# 23005_5.net
KiCad netlist of a schematic drawn in Altium Designer
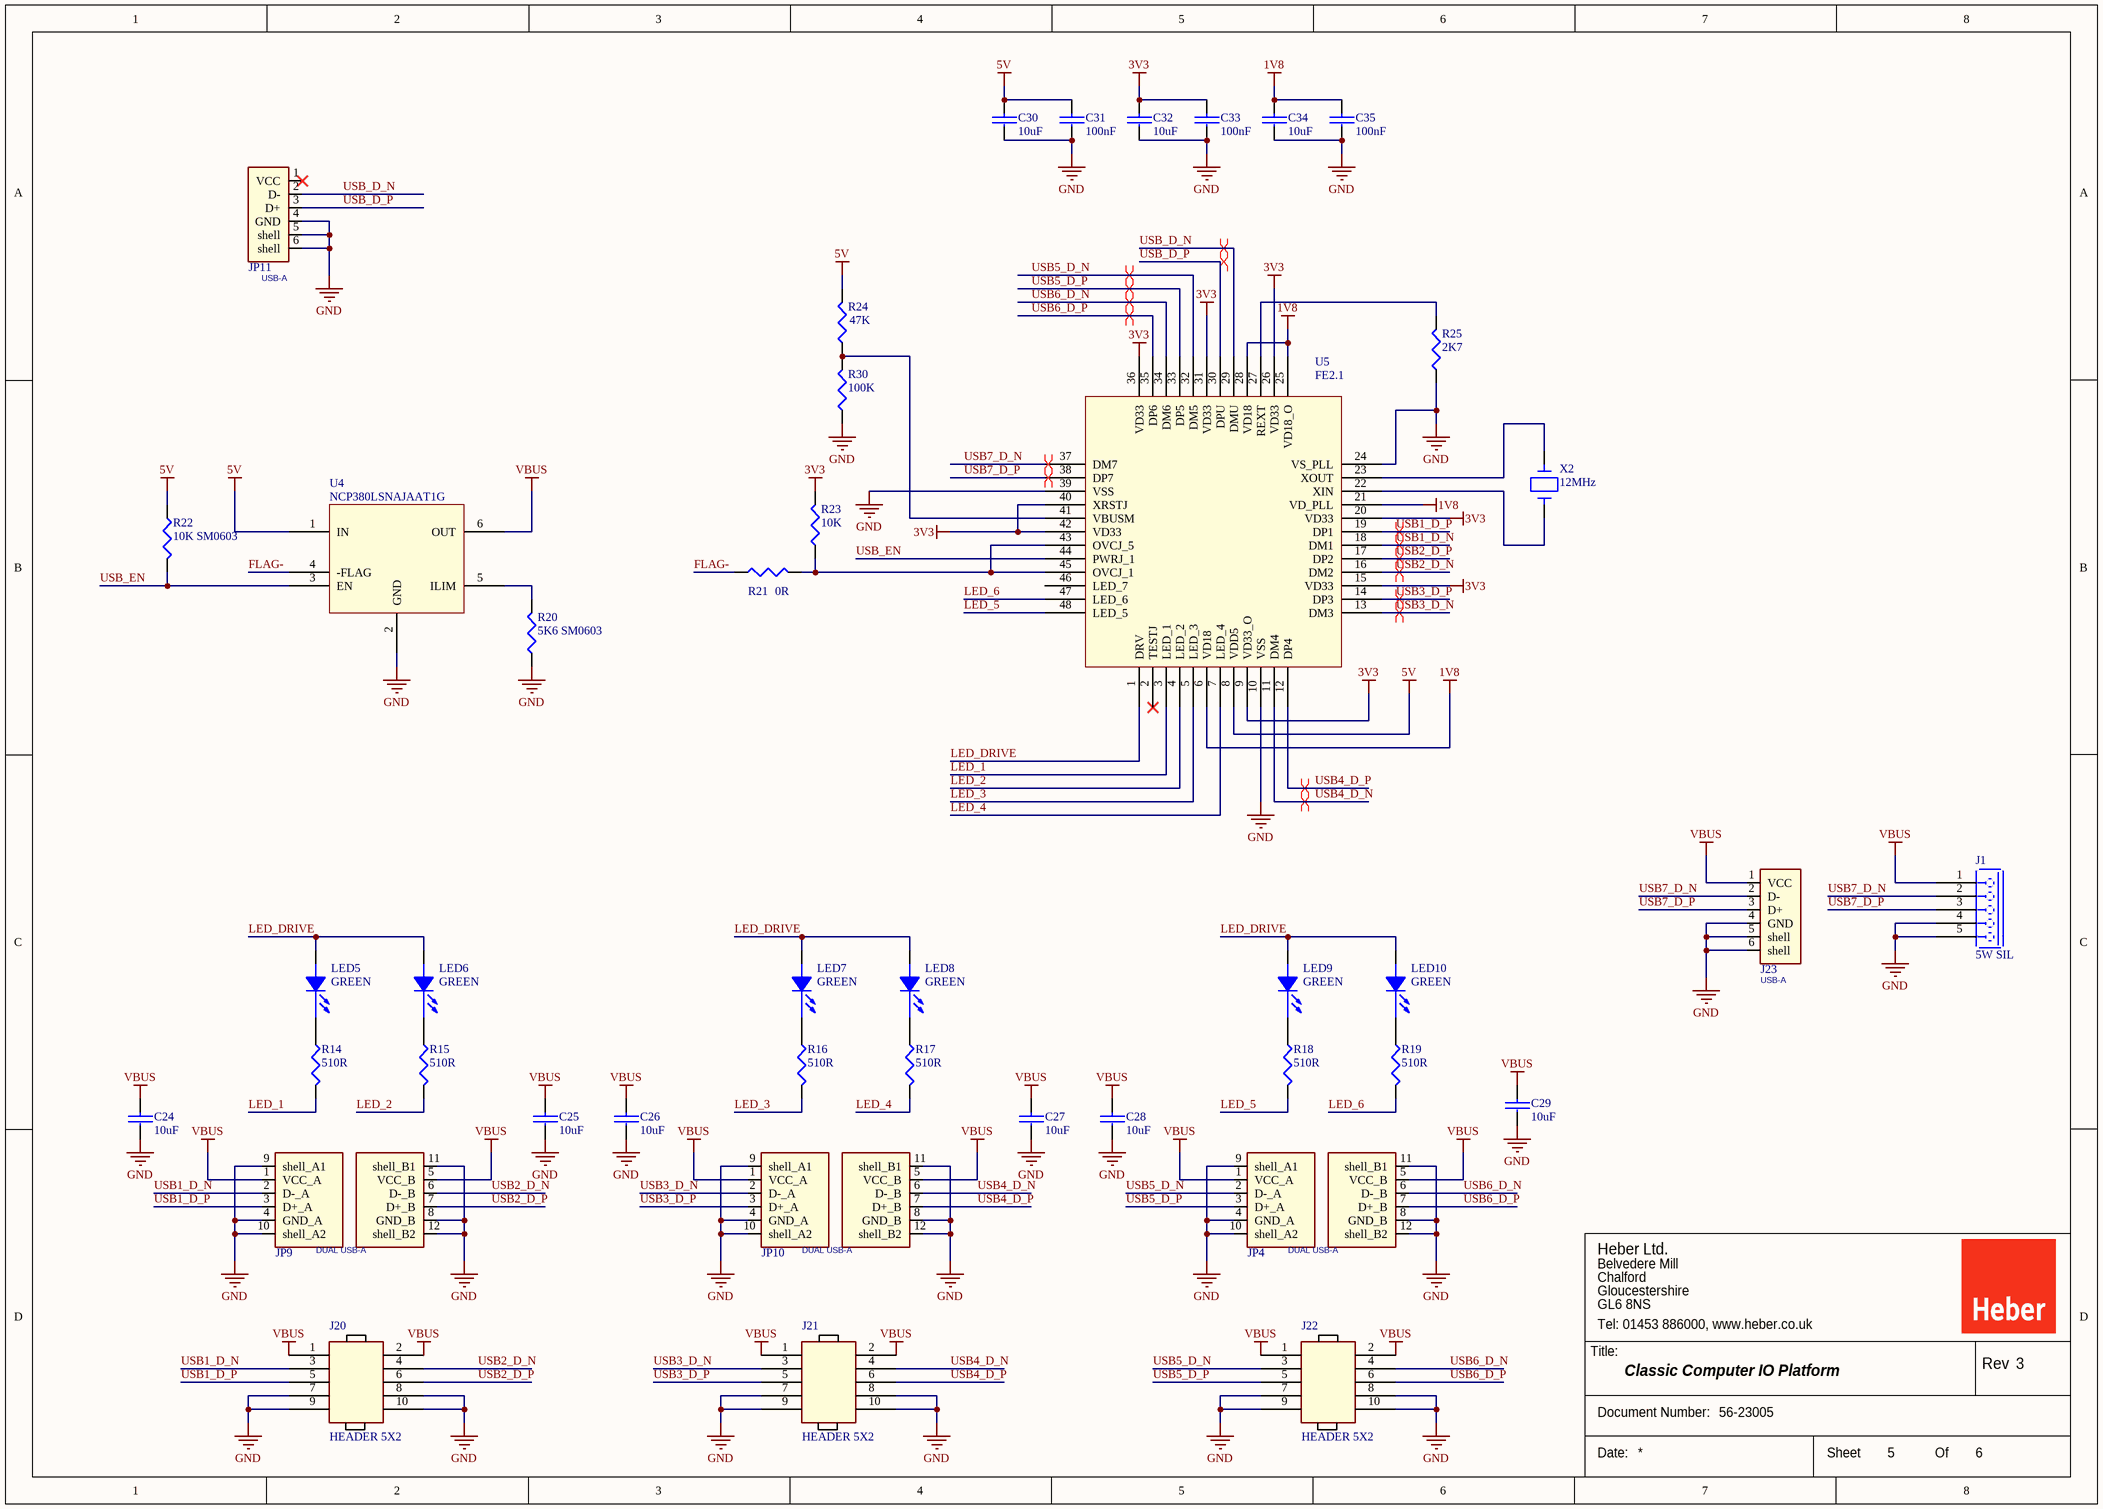
[diagram p0: 23005_5.SchDoc]

(export (version "E")
  (design (tool "Eeschema 10.0.6"))
  (components
    (comp (ref "C24") (value "10uF") (footprint "SM0805") (libsource (lib "LIBRARY1_Library") (part "C")))
    (comp (ref "C25") (value "10uF") (footprint "SM0805") (libsource (lib "LIBRARY1_Library") (part "C")))
    (comp (ref "C26") (value "10uF") (footprint "SM0805") (libsource (lib "LIBRARY1_Library") (part "C")))
    (comp (ref "C27") (value "10uF") (footprint "SM0805") (libsource (lib "LIBRARY1_Library") (part "C")))
    (comp (ref "C28") (value "10uF") (footprint "SM0805") (libsource (lib "LIBRARY1_Library") (part "C")))
    (comp (ref "C29") (value "10uF") (footprint "SM0805") (libsource (lib "LIBRARY1_Library") (part "C")))
    (comp (ref "C30") (value "10uF") (footprint "SM0805") (libsource (lib "LIBRARY1_Library") (part "C")))
    (comp (ref "C31") (value "100nF") (footprint "SM0603") (libsource (lib "LIBRARY1_Library") (part "C")))
    (comp (ref "C32") (value "10uF") (footprint "SM0805") (libsource (lib "LIBRARY1_Library") (part "C")))
    (comp (ref "C33") (value "100nF") (footprint "SM0603") (libsource (lib "LIBRARY1_Library") (part "C")))
    (comp (ref "C34") (value "10uF") (footprint "SM0805") (libsource (lib "LIBRARY1_Library") (part "C")))
    (comp (ref "C35") (value "100nF") (footprint "SM0603") (libsource (lib "LIBRARY1_Library") (part "C")))
    (comp (ref "J1")
      (value "5W SIL")
      (footprint "5WSIL")
      (libsource (lib "LIBRARY1_Library") (part "HEADER 5W SIL"))
    )
    (comp (ref "J20")
      (value "HEADER 5X2")
      (footprint "10WHDR_5X2")
      (libsource (lib "LIBRARY1_Library") (part "HEADER 5X2"))
    )
    (comp (ref "J21")
      (value "HEADER 5X2")
      (footprint "10WHDR_5X2")
      (libsource (lib "LIBRARY1_Library") (part "HEADER 5X2"))
    )
    (comp (ref "J22")
      (value "HEADER 5X2")
      (footprint "10WHDR_5X2")
      (libsource (lib "LIBRARY1_Library") (part "HEADER 5X2"))
    )
    (comp (ref "J23")
      (value "USB-A")
      (footprint "USB_WURTH_61400416021")
      (libsource (lib "LIBRARY1_Library") (part "USB-A"))
    )
    (comp (ref "JP4")
      (value "DUAL USB-A")
      (footprint "USB_STACK")
      (libsource (lib "LIBRARY1_Library") (part "USB-A_DUAL"))
    )
    (comp (ref "JP9")
      (value "DUAL USB-A")
      (footprint "USB_STACK")
      (libsource (lib "LIBRARY1_Library") (part "USB-A_DUAL"))
    )
    (comp (ref "JP10")
      (value "DUAL USB-A")
      (footprint "USB_STACK")
      (libsource (lib "LIBRARY1_Library") (part "USB-A_DUAL"))
    )
    (comp (ref "JP11")
      (value "USB-A")
      (footprint "USB_WURTH_61400416021")
      (libsource (lib "") (part "USB-A_1"))
    )
    (comp (ref "LED5")
      (value "GREEN")
      (footprint "SM0603LED_1")
      (libsource (lib "LIBRARY1_Library") (part "LED"))
    )
    (comp (ref "LED6")
      (value "GREEN")
      (footprint "SM0603LED_1")
      (libsource (lib "LIBRARY1_Library") (part "LED"))
    )
    (comp (ref "LED7")
      (value "GREEN")
      (footprint "SM0603LED_1")
      (libsource (lib "LIBRARY1_Library") (part "LED"))
    )
    (comp (ref "LED8")
      (value "GREEN")
      (footprint "SM0603LED_1")
      (libsource (lib "LIBRARY1_Library") (part "LED"))
    )
    (comp (ref "LED9")
      (value "GREEN")
      (footprint "SM0603LED_1")
      (libsource (lib "LIBRARY1_Library") (part "LED"))
    )
    (comp (ref "LED10")
      (value "GREEN")
      (footprint "SM0603LED_1")
      (libsource (lib "LIBRARY1_Library") (part "LED"))
    )
    (comp (ref "R14") (value "510R") (footprint "SM0603") (libsource (lib "LIBRARY1_Library") (part "RES")))
    (comp (ref "R15") (value "510R") (footprint "SM0603") (libsource (lib "LIBRARY1_Library") (part "RES")))
    (comp (ref "R16") (value "510R") (footprint "SM0603") (libsource (lib "LIBRARY1_Library") (part "RES")))
    (comp (ref "R17") (value "510R") (footprint "SM0603") (libsource (lib "LIBRARY1_Library") (part "RES")))
    (comp (ref "R18") (value "510R") (footprint "SM0603") (libsource (lib "LIBRARY1_Library") (part "RES")))
    (comp (ref "R19") (value "510R") (footprint "SM0603") (libsource (lib "LIBRARY1_Library") (part "RES")))
    (comp (ref "R20")
      (value "5K6 SM0603")
      (footprint "SM0603")
      (libsource (lib "LIBRARY1_Library") (part "RES"))
    )
    (comp (ref "R21") (value "0R") (footprint "SM0603") (libsource (lib "LIBRARY1_Library") (part "RES")))
    (comp (ref "R22")
      (value "10K SM0603")
      (footprint "SM0603")
      (libsource (lib "LIBRARY1_Library") (part "RES"))
    )
    (comp (ref "R23") (value "10K") (footprint "SM0603") (libsource (lib "LIBRARY1_Library") (part "RES")))
    (comp (ref "R24") (value "47K") (footprint "SM0603") (libsource (lib "LIBRARY1_Library") (part "RES")))
    (comp (ref "R25") (value "2K7") (footprint "SM0603") (libsource (lib "LIBRARY1_Library") (part "RES")))
    (comp (ref "R30") (value "100K") (footprint "SM0603") (libsource (lib "LIBRARY1_Library") (part "RES")))
    (comp (ref "U4")
      (value "NCP380LSNAJAAT1G")
      (footprint "SOT23-6LEAD")
      (libsource (lib "LIBRARY1_Library") (part "NCP380LSNAJAAT1G"))
    )
    (comp (ref "U5") (value "FE2.1") (footprint "LQFP48") (libsource (lib "LIBRARY1_Library") (part "FE2.1")))
    (comp (ref "X2") (value "12MHz") (footprint "HC49_I3") (libsource (lib "LIBRARY1_Library") (part "XTAL")))
  )
  (nets
    (net (code "1") (name "/FLAG-") (class "Default")
      (node (ref "R21") (pin "1") (pinfunction "1_1") (pintype "passive"))
      (node (ref "U4") (pin "4") (pinfunction "-FLAG_4") (pintype "passive"))
    )
    (net (code "2") (name "/LED_1") (class "Default")
      (node (ref "R14") (pin "2") (pinfunction "2_2") (pintype "passive"))
      (node (ref "U5") (pin "3") (pinfunction "LED_1_3") (pintype "passive"))
    )
    (net (code "3") (name "/LED_2") (class "Default")
      (node (ref "R15") (pin "2") (pinfunction "2_2") (pintype "passive"))
      (node (ref "U5") (pin "4") (pinfunction "LED_2_4") (pintype "passive"))
    )
    (net (code "4") (name "/LED_3") (class "Default")
      (node (ref "R16") (pin "2") (pinfunction "2_2") (pintype "passive"))
      (node (ref "U5") (pin "5") (pinfunction "LED_3_5") (pintype "passive"))
    )
    (net (code "5") (name "/LED_4") (class "Default")
      (node (ref "R17") (pin "2") (pinfunction "2_2") (pintype "passive"))
      (node (ref "U5") (pin "7") (pinfunction "LED_4_7") (pintype "passive"))
    )
    (net (code "6") (name "/LED_5") (class "Default")
      (node (ref "R18") (pin "2") (pinfunction "2_2") (pintype "passive"))
      (node (ref "U5") (pin "48") (pinfunction "LED_5_48") (pintype "passive"))
    )
    (net (code "7") (name "/LED_6") (class "Default")
      (node (ref "R19") (pin "2") (pinfunction "2_2") (pintype "passive"))
      (node (ref "U5") (pin "47") (pinfunction "LED_6_47") (pintype "passive"))
    )
    (net (code "8") (name "/LED_DRIVE") (class "Default")
      (node (ref "LED10") (pin "1") (pinfunction "ANODE_1") (pintype "passive"))
      (node (ref "LED5") (pin "1") (pinfunction "ANODE_1") (pintype "passive"))
      (node (ref "LED6") (pin "1") (pinfunction "ANODE_1") (pintype "passive"))
      (node (ref "LED7") (pin "1") (pinfunction "ANODE_1") (pintype "passive"))
      (node (ref "LED8") (pin "1") (pinfunction "ANODE_1") (pintype "passive"))
      (node (ref "LED9") (pin "1") (pinfunction "ANODE_1") (pintype "passive"))
      (node (ref "U5") (pin "1") (pinfunction "DRV_1") (pintype "passive"))
    )
    (net (code "9") (name "/USB1_D_N") (class "Default")
      (node (ref "J20") (pin "3") (pinfunction "3_3") (pintype "passive"))
      (node (ref "JP9") (pin "2") (pinfunction "D-_A_2") (pintype "passive"))
      (node (ref "U5") (pin "18") (pinfunction "DM1_18") (pintype "passive"))
    )
    (net (code "10") (name "/USB1_D_P") (class "Default")
      (node (ref "J20") (pin "5") (pinfunction "5_5") (pintype "passive"))
      (node (ref "JP9") (pin "3") (pinfunction "D+_A_3") (pintype "passive"))
      (node (ref "U5") (pin "19") (pinfunction "DP1_19") (pintype "passive"))
    )
    (net (code "11") (name "/USB2_D_N") (class "Default")
      (node (ref "J20") (pin "4") (pinfunction "4_4") (pintype "passive"))
      (node (ref "JP9") (pin "6") (pinfunction "D-_B_6") (pintype "passive"))
      (node (ref "U5") (pin "16") (pinfunction "DM2_16") (pintype "passive"))
    )
    (net (code "12") (name "/USB2_D_P") (class "Default")
      (node (ref "J20") (pin "6") (pinfunction "6_6") (pintype "passive"))
      (node (ref "JP9") (pin "7") (pinfunction "D+_B_7") (pintype "passive"))
      (node (ref "U5") (pin "17") (pinfunction "DP2_17") (pintype "passive"))
    )
    (net (code "13") (name "/USB3_D_N") (class "Default")
      (node (ref "J21") (pin "3") (pinfunction "3_3") (pintype "passive"))
      (node (ref "JP10") (pin "2") (pinfunction "D-_A_2") (pintype "passive"))
      (node (ref "U5") (pin "13") (pinfunction "DM3_13") (pintype "passive"))
    )
    (net (code "14") (name "/USB3_D_P") (class "Default")
      (node (ref "J21") (pin "5") (pinfunction "5_5") (pintype "passive"))
      (node (ref "JP10") (pin "3") (pinfunction "D+_A_3") (pintype "passive"))
      (node (ref "U5") (pin "14") (pinfunction "DP3_14") (pintype "passive"))
    )
    (net (code "15") (name "/USB4_D_N") (class "Default")
      (node (ref "J21") (pin "4") (pinfunction "4_4") (pintype "passive"))
      (node (ref "JP10") (pin "6") (pinfunction "D-_B_6") (pintype "passive"))
      (node (ref "U5") (pin "11") (pinfunction "DM4_11") (pintype "passive"))
    )
    (net (code "16") (name "/USB4_D_P") (class "Default")
      (node (ref "J21") (pin "6") (pinfunction "6_6") (pintype "passive"))
      (node (ref "JP10") (pin "7") (pinfunction "D+_B_7") (pintype "passive"))
      (node (ref "U5") (pin "12") (pinfunction "DP4_12") (pintype "passive"))
    )
    (net (code "17") (name "/USB5_D_N") (class "Default")
      (node (ref "J22") (pin "3") (pinfunction "3_3") (pintype "passive"))
      (node (ref "JP4") (pin "2") (pinfunction "D-_A_2") (pintype "passive"))
      (node (ref "U5") (pin "32") (pinfunction "DM5_32") (pintype "passive"))
    )
    (net (code "18") (name "/USB5_D_P") (class "Default")
      (node (ref "J22") (pin "5") (pinfunction "5_5") (pintype "passive"))
      (node (ref "JP4") (pin "3") (pinfunction "D+_A_3") (pintype "passive"))
      (node (ref "U5") (pin "33") (pinfunction "DP5_33") (pintype "passive"))
    )
    (net (code "19") (name "/USB6_D_N") (class "Default")
      (node (ref "J22") (pin "4") (pinfunction "4_4") (pintype "passive"))
      (node (ref "JP4") (pin "6") (pinfunction "D-_B_6") (pintype "passive"))
      (node (ref "U5") (pin "34") (pinfunction "DM6_34") (pintype "passive"))
    )
    (net (code "20") (name "/USB6_D_P") (class "Default")
      (node (ref "J22") (pin "6") (pinfunction "6_6") (pintype "passive"))
      (node (ref "JP4") (pin "7") (pinfunction "D+_B_7") (pintype "passive"))
      (node (ref "U5") (pin "35") (pinfunction "DP6_35") (pintype "passive"))
    )
    (net (code "21") (name "/USB7_D_N") (class "Default")
      (node (ref "J1") (pin "2") (pinfunction "2_2") (pintype "passive"))
      (node (ref "J23") (pin "2") (pinfunction "D-_2") (pintype "passive"))
      (node (ref "U5") (pin "37") (pinfunction "DM7_37") (pintype "passive"))
    )
    (net (code "22") (name "/USB7_D_P") (class "Default")
      (node (ref "J1") (pin "3") (pinfunction "3_3") (pintype "passive"))
      (node (ref "J23") (pin "3") (pinfunction "D+_3") (pintype "passive"))
      (node (ref "U5") (pin "38") (pinfunction "DP7_38") (pintype "passive"))
    )
    (net (code "23") (name "/USB_D_N") (class "Default")
      (node (ref "JP11") (pin "2") (pinfunction "D-_2") (pintype "passive"))
      (node (ref "U5") (pin "29") (pinfunction "DMU_29") (pintype "passive"))
    )
    (net (code "24") (name "/USB_D_P") (class "Default")
      (node (ref "JP11") (pin "3") (pinfunction "D+_3") (pintype "passive"))
      (node (ref "U5") (pin "30") (pinfunction "DPU_30") (pintype "passive"))
    )
    (net (code "25") (name "/USB_EN") (class "Default")
      (node (ref "R22") (pin "2") (pinfunction "2_2") (pintype "passive"))
      (node (ref "U4") (pin "3") (pinfunction "EN_3") (pintype "passive"))
      (node (ref "U5") (pin "44") (pinfunction "PWRJ_1_44") (pintype "passive"))
    )
    (net (code "26") (name "1V8") (class "Default")
      (node (ref "C34") (pin "1") (pinfunction "1_1") (pintype "passive"))
      (node (ref "C35") (pin "1") (pinfunction "1_1") (pintype "passive"))
      (node (ref "U5") (pin "21") (pinfunction "VD_PLL_21") (pintype "passive"))
      (node (ref "U5") (pin "25") (pinfunction "VD18_O_25") (pintype "passive"))
      (node (ref "U5") (pin "28") (pinfunction "VD18_28") (pintype "passive"))
      (node (ref "U5") (pin "6") (pinfunction "VD18_6") (pintype "passive"))
    )
    (net (code "27") (name "3V3") (class "Default")
      (node (ref "C32") (pin "1") (pinfunction "1_1") (pintype "passive"))
      (node (ref "C33") (pin "1") (pinfunction "1_1") (pintype "passive"))
      (node (ref "R23") (pin "2") (pinfunction "2_2") (pintype "passive"))
      (node (ref "U5") (pin "15") (pinfunction "VD33_15") (pintype "passive"))
      (node (ref "U5") (pin "20") (pinfunction "VD33_20") (pintype "passive"))
      (node (ref "U5") (pin "26") (pinfunction "VD33_26") (pintype "passive"))
      (node (ref "U5") (pin "31") (pinfunction "VD33_31") (pintype "passive"))
      (node (ref "U5") (pin "36") (pinfunction "VD33_36") (pintype "passive"))
      (node (ref "U5") (pin "40") (pinfunction "XRSTJ_40") (pintype "passive"))
      (node (ref "U5") (pin "42") (pinfunction "VD33_42") (pintype "passive"))
      (node (ref "U5") (pin "9") (pinfunction "VD33_O_9") (pintype "passive"))
    )
    (net (code "28") (name "5V") (class "Default")
      (node (ref "C30") (pin "1") (pinfunction "1_1") (pintype "passive"))
      (node (ref "C31") (pin "1") (pinfunction "1_1") (pintype "passive"))
      (node (ref "R22") (pin "1") (pinfunction "1_1") (pintype "passive"))
      (node (ref "R24") (pin "2") (pinfunction "2_2") (pintype "passive"))
      (node (ref "U4") (pin "1") (pinfunction "IN_1") (pintype "passive"))
      (node (ref "U5") (pin "8") (pinfunction "VDD5_8") (pintype "passive"))
    )
    (net (code "29") (name "GND") (class "Default")
      (node (ref "C24") (pin "2") (pinfunction "2_2") (pintype "passive"))
      (node (ref "C25") (pin "2") (pinfunction "2_2") (pintype "passive"))
      (node (ref "C26") (pin "2") (pinfunction "2_2") (pintype "passive"))
      (node (ref "C27") (pin "2") (pinfunction "2_2") (pintype "passive"))
      (node (ref "C28") (pin "2") (pinfunction "2_2") (pintype "passive"))
      (node (ref "C29") (pin "2") (pinfunction "2_2") (pintype "passive"))
      (node (ref "C30") (pin "2") (pinfunction "2_2") (pintype "passive"))
      (node (ref "C31") (pin "2") (pinfunction "2_2") (pintype "passive"))
      (node (ref "C32") (pin "2") (pinfunction "2_2") (pintype "passive"))
      (node (ref "C33") (pin "2") (pinfunction "2_2") (pintype "passive"))
      (node (ref "C34") (pin "2") (pinfunction "2_2") (pintype "passive"))
      (node (ref "C35") (pin "2") (pinfunction "2_2") (pintype "passive"))
      (node (ref "J1") (pin "4") (pinfunction "4_4") (pintype "passive"))
      (node (ref "J1") (pin "5") (pinfunction "5_5") (pintype "passive"))
      (node (ref "J20") (pin "10") (pinfunction "10_10") (pintype "passive"))
      (node (ref "J20") (pin "7") (pinfunction "7_7") (pintype "passive"))
      (node (ref "J20") (pin "8") (pinfunction "8_8") (pintype "passive"))
      (node (ref "J20") (pin "9") (pinfunction "9_9") (pintype "passive"))
      (node (ref "J21") (pin "10") (pinfunction "10_10") (pintype "passive"))
      (node (ref "J21") (pin "7") (pinfunction "7_7") (pintype "passive"))
      (node (ref "J21") (pin "8") (pinfunction "8_8") (pintype "passive"))
      (node (ref "J21") (pin "9") (pinfunction "9_9") (pintype "passive"))
      (node (ref "J22") (pin "10") (pinfunction "10_10") (pintype "passive"))
      (node (ref "J22") (pin "7") (pinfunction "7_7") (pintype "passive"))
      (node (ref "J22") (pin "8") (pinfunction "8_8") (pintype "passive"))
      (node (ref "J22") (pin "9") (pinfunction "9_9") (pintype "passive"))
      (node (ref "J23") (pin "4") (pinfunction "GND_4") (pintype "passive"))
      (node (ref "J23") (pin "5") (pinfunction "shell_5") (pintype "passive"))
      (node (ref "J23") (pin "6") (pinfunction "shell_6") (pintype "passive"))
      (node (ref "JP10") (pin "10") (pinfunction "shell_A2_10") (pintype "passive"))
      (node (ref "JP10") (pin "11") (pinfunction "shell_B1_11") (pintype "passive"))
      (node (ref "JP10") (pin "12") (pinfunction "shell_B2_12") (pintype "passive"))
      (node (ref "JP10") (pin "4") (pinfunction "GND_A_4") (pintype "passive"))
      (node (ref "JP10") (pin "8") (pinfunction "GND_B_8") (pintype "passive"))
      (node (ref "JP10") (pin "9") (pinfunction "shell_A1_9") (pintype "passive"))
      (node (ref "JP11") (pin "4") (pinfunction "GND_4") (pintype "passive"))
      (node (ref "JP11") (pin "5") (pinfunction "shell_5") (pintype "passive"))
      (node (ref "JP11") (pin "6") (pinfunction "shell_6") (pintype "passive"))
      (node (ref "JP4") (pin "10") (pinfunction "shell_A2_10") (pintype "passive"))
      (node (ref "JP4") (pin "11") (pinfunction "shell_B1_11") (pintype "passive"))
      (node (ref "JP4") (pin "12") (pinfunction "shell_B2_12") (pintype "passive"))
      (node (ref "JP4") (pin "4") (pinfunction "GND_A_4") (pintype "passive"))
      (node (ref "JP4") (pin "8") (pinfunction "GND_B_8") (pintype "passive"))
      (node (ref "JP4") (pin "9") (pinfunction "shell_A1_9") (pintype "passive"))
      (node (ref "JP9") (pin "10") (pinfunction "shell_A2_10") (pintype "passive"))
      (node (ref "JP9") (pin "11") (pinfunction "shell_B1_11") (pintype "passive"))
      (node (ref "JP9") (pin "12") (pinfunction "shell_B2_12") (pintype "passive"))
      (node (ref "JP9") (pin "4") (pinfunction "GND_A_4") (pintype "passive"))
      (node (ref "JP9") (pin "8") (pinfunction "GND_B_8") (pintype "passive"))
      (node (ref "JP9") (pin "9") (pinfunction "shell_A1_9") (pintype "passive"))
      (node (ref "R20") (pin "1") (pinfunction "1_1") (pintype "passive"))
      (node (ref "R25") (pin "1") (pinfunction "1_1") (pintype "passive"))
      (node (ref "R30") (pin "1") (pinfunction "1_1") (pintype "passive"))
      (node (ref "U4") (pin "2") (pinfunction "GND_2") (pintype "passive"))
      (node (ref "U5") (pin "10") (pinfunction "VSS_10") (pintype "passive"))
      (node (ref "U5") (pin "24") (pinfunction "VS_PLL_24") (pintype "passive"))
      (node (ref "U5") (pin "39") (pinfunction "VSS_39") (pintype "passive"))
    )
    (net (code "30") (name "Net-(LED5-CATHODE)") (class "Default")
      (node (ref "LED5") (pin "2") (pinfunction "CATHODE_2") (pintype "passive"))
      (node (ref "R14") (pin "1") (pinfunction "1_1") (pintype "passive"))
    )
    (net (code "31") (name "Net-(LED6-CATHODE)") (class "Default")
      (node (ref "LED6") (pin "2") (pinfunction "CATHODE_2") (pintype "passive"))
      (node (ref "R15") (pin "1") (pinfunction "1_1") (pintype "passive"))
    )
    (net (code "32") (name "Net-(LED7-CATHODE)") (class "Default")
      (node (ref "LED7") (pin "2") (pinfunction "CATHODE_2") (pintype "passive"))
      (node (ref "R16") (pin "1") (pinfunction "1_1") (pintype "passive"))
    )
    (net (code "33") (name "Net-(LED8-CATHODE)") (class "Default")
      (node (ref "LED8") (pin "2") (pinfunction "CATHODE_2") (pintype "passive"))
      (node (ref "R17") (pin "1") (pinfunction "1_1") (pintype "passive"))
    )
    (net (code "34") (name "Net-(LED9-CATHODE)") (class "Default")
      (node (ref "LED9") (pin "2") (pinfunction "CATHODE_2") (pintype "passive"))
      (node (ref "R18") (pin "1") (pinfunction "1_1") (pintype "passive"))
    )
    (net (code "35") (name "Net-(LED10-CATHODE)") (class "Default")
      (node (ref "LED10") (pin "2") (pinfunction "CATHODE_2") (pintype "passive"))
      (node (ref "R19") (pin "1") (pinfunction "1_1") (pintype "passive"))
    )
    (net (code "36") (name "Net-(U4-ILIM)") (class "Default")
      (node (ref "R20") (pin "2") (pinfunction "2_2") (pintype "passive"))
      (node (ref "U4") (pin "5") (pinfunction "ILIM_5") (pintype "passive"))
    )
    (net (code "37") (name "Net-(U5-OVCJ_1)") (class "Default")
      (node (ref "R21") (pin "2") (pinfunction "2_2") (pintype "passive"))
      (node (ref "R23") (pin "1") (pinfunction "1_1") (pintype "passive"))
      (node (ref "U5") (pin "43") (pinfunction "OVCJ_5_43") (pintype "passive"))
      (node (ref "U5") (pin "45") (pinfunction "OVCJ_1_45") (pintype "passive"))
    )
    (net (code "38") (name "Net-(U5-REXT)") (class "Default")
      (node (ref "R25") (pin "2") (pinfunction "2_2") (pintype "passive"))
      (node (ref "U5") (pin "27") (pinfunction "REXT_27") (pintype "passive"))
    )
    (net (code "39") (name "Net-(U5-VBUSM)") (class "Default")
      (node (ref "R24") (pin "1") (pinfunction "1_1") (pintype "passive"))
      (node (ref "R30") (pin "2") (pinfunction "2_2") (pintype "passive"))
      (node (ref "U5") (pin "41") (pinfunction "VBUSM_41") (pintype "passive"))
    )
    (net (code "40") (name "Net-(U5-XIN)") (class "Default")
      (node (ref "U5") (pin "22") (pinfunction "XIN_22") (pintype "passive"))
      (node (ref "X2") (pin "2") (pinfunction "2_2") (pintype "passive"))
    )
    (net (code "41") (name "Net-(U5-XOUT)") (class "Default")
      (node (ref "U5") (pin "23") (pinfunction "XOUT_23") (pintype "passive"))
      (node (ref "X2") (pin "1") (pinfunction "1_1") (pintype "passive"))
    )
    (net (code "42") (name "VBUS") (class "Default")
      (node (ref "C24") (pin "1") (pinfunction "1_1") (pintype "passive"))
      (node (ref "C25") (pin "1") (pinfunction "1_1") (pintype "passive"))
      (node (ref "C26") (pin "1") (pinfunction "1_1") (pintype "passive"))
      (node (ref "C27") (pin "1") (pinfunction "1_1") (pintype "passive"))
      (node (ref "C28") (pin "1") (pinfunction "1_1") (pintype "passive"))
      (node (ref "C29") (pin "1") (pinfunction "1_1") (pintype "passive"))
      (node (ref "J1") (pin "1") (pinfunction "1_1") (pintype "passive"))
      (node (ref "J20") (pin "1") (pinfunction "1_1") (pintype "passive"))
      (node (ref "J20") (pin "2") (pinfunction "2_2") (pintype "passive"))
      (node (ref "J21") (pin "1") (pinfunction "1_1") (pintype "passive"))
      (node (ref "J21") (pin "2") (pinfunction "2_2") (pintype "passive"))
      (node (ref "J22") (pin "1") (pinfunction "1_1") (pintype "passive"))
      (node (ref "J22") (pin "2") (pinfunction "2_2") (pintype "passive"))
      (node (ref "J23") (pin "1") (pinfunction "VCC_1") (pintype "passive"))
      (node (ref "JP10") (pin "1") (pinfunction "VCC_A_1") (pintype "passive"))
      (node (ref "JP10") (pin "5") (pinfunction "VCC_B_5") (pintype "passive"))
      (node (ref "JP4") (pin "1") (pinfunction "VCC_A_1") (pintype "passive"))
      (node (ref "JP4") (pin "5") (pinfunction "VCC_B_5") (pintype "passive"))
      (node (ref "JP9") (pin "1") (pinfunction "VCC_A_1") (pintype "passive"))
      (node (ref "JP9") (pin "5") (pinfunction "VCC_B_5") (pintype "passive"))
      (node (ref "U4") (pin "6") (pinfunction "OUT_6") (pintype "passive"))
    )
    (net (code "43") (name "unconnected-(JP11-VCC-Pad1)") (class "Default")
      (node (ref "JP11") (pin "1") (pinfunction "VCC_1") (pintype "passive+no_connect"))
    )
    (net (code "44") (name "unconnected-(U5-LED_7-Pad46)") (class "Default")
      (node (ref "U5") (pin "46") (pinfunction "LED_7_46") (pintype "passive"))
    )
    (net (code "45") (name "unconnected-(U5-TESTJ-Pad2)") (class "Default")
      (node (ref "U5") (pin "2") (pinfunction "TESTJ_2") (pintype "passive+no_connect"))
    )
  )
)
